# R131X.net
KiCad netlist of a schematic drawn in EAGLE
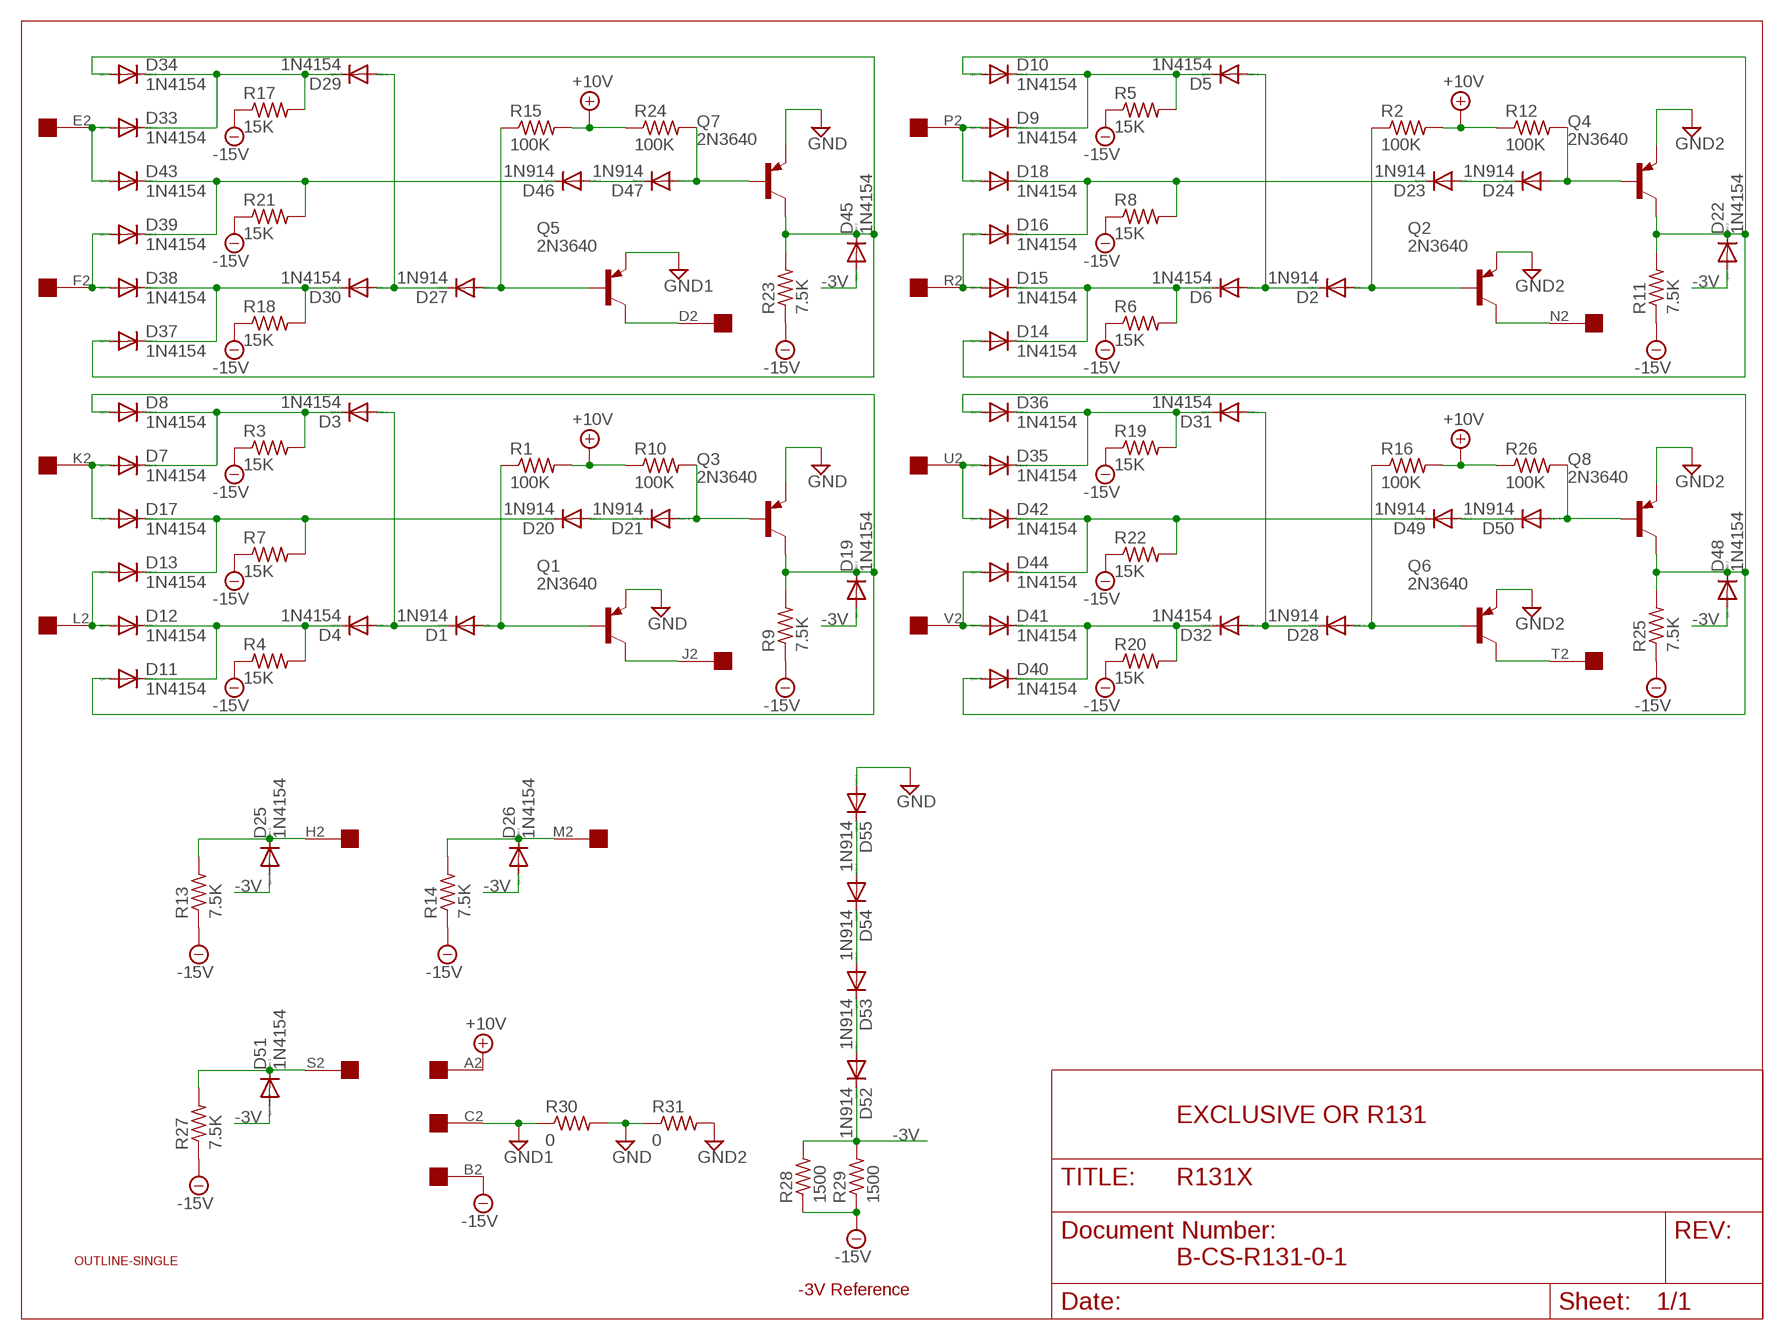
[diagram p0: schematic, sheet 1]

(export (version "E")
  (design (tool "Eeschema 10.0.6"))
  (components
    (comp (ref "D1")
      (value "1N914")
      (footprint "eagle-import:DO35-10")
      (libsource (lib "eagle-import") (part "1N4148DO35-10"))
    )
    (comp (ref "D2")
      (value "1N914")
      (footprint "eagle-import:DO35-10")
      (libsource (lib "eagle-import") (part "1N4148DO35-10"))
    )
    (comp (ref "D3")
      (value "1N4154")
      (footprint "eagle-import:DO35-10")
      (libsource (lib "eagle-import") (part "1N4148DO35-10"))
    )
    (comp (ref "D4")
      (value "1N4154")
      (footprint "eagle-import:DO35-10")
      (libsource (lib "eagle-import") (part "1N4148DO35-10"))
    )
    (comp (ref "D5")
      (value "1N4154")
      (footprint "eagle-import:DO35-10")
      (libsource (lib "eagle-import") (part "1N4148DO35-10"))
    )
    (comp (ref "D6")
      (value "1N4154")
      (footprint "eagle-import:DO35-10")
      (libsource (lib "eagle-import") (part "1N4148DO35-10"))
    )
    (comp (ref "D7")
      (value "1N4154")
      (footprint "eagle-import:DO35-10")
      (libsource (lib "eagle-import") (part "1N4148DO35-10"))
    )
    (comp (ref "D8")
      (value "1N4154")
      (footprint "eagle-import:DO35-10")
      (libsource (lib "eagle-import") (part "1N4148DO35-10"))
    )
    (comp (ref "D9")
      (value "1N4154")
      (footprint "eagle-import:DO35-10")
      (libsource (lib "eagle-import") (part "1N4148DO35-10"))
    )
    (comp (ref "D10")
      (value "1N4154")
      (footprint "eagle-import:DO35-10")
      (libsource (lib "eagle-import") (part "1N4148DO35-10"))
    )
    (comp (ref "D11")
      (value "1N4154")
      (footprint "eagle-import:DO35-10")
      (libsource (lib "eagle-import") (part "1N4148DO35-10"))
    )
    (comp (ref "D12")
      (value "1N4154")
      (footprint "eagle-import:DO35-10")
      (libsource (lib "eagle-import") (part "1N4148DO35-10"))
    )
    (comp (ref "D13")
      (value "1N4154")
      (footprint "eagle-import:DO35-10")
      (libsource (lib "eagle-import") (part "1N4148DO35-10"))
    )
    (comp (ref "D14")
      (value "1N4154")
      (footprint "eagle-import:DO35-10")
      (libsource (lib "eagle-import") (part "1N4148DO35-10"))
    )
    (comp (ref "D15")
      (value "1N4154")
      (footprint "eagle-import:DO35-10")
      (libsource (lib "eagle-import") (part "1N4148DO35-10"))
    )
    (comp (ref "D16")
      (value "1N4154")
      (footprint "eagle-import:DO35-10")
      (libsource (lib "eagle-import") (part "1N4148DO35-10"))
    )
    (comp (ref "D17")
      (value "1N4154")
      (footprint "eagle-import:DO35-10")
      (libsource (lib "eagle-import") (part "1N4148DO35-10"))
    )
    (comp (ref "D18")
      (value "1N4154")
      (footprint "eagle-import:DO35-10")
      (libsource (lib "eagle-import") (part "1N4148DO35-10"))
    )
    (comp (ref "D19")
      (value "1N4154")
      (footprint "eagle-import:DO35-10")
      (libsource (lib "eagle-import") (part "1N4148DO35-10"))
    )
    (comp (ref "D20")
      (value "1N914")
      (footprint "eagle-import:DO35-10")
      (libsource (lib "eagle-import") (part "1N4148DO35-10"))
    )
    (comp (ref "D21")
      (value "1N914")
      (footprint "eagle-import:DO35-10")
      (libsource (lib "eagle-import") (part "1N4148DO35-10"))
    )
    (comp (ref "D22")
      (value "1N4154")
      (footprint "eagle-import:DO35-10")
      (libsource (lib "eagle-import") (part "1N4148DO35-10"))
    )
    (comp (ref "D23")
      (value "1N914")
      (footprint "eagle-import:DO35-10")
      (libsource (lib "eagle-import") (part "1N4148DO35-10"))
    )
    (comp (ref "D24")
      (value "1N914")
      (footprint "eagle-import:DO35-10")
      (libsource (lib "eagle-import") (part "1N4148DO35-10"))
    )
    (comp (ref "D25")
      (value "1N4154")
      (footprint "eagle-import:DO35-10")
      (libsource (lib "eagle-import") (part "1N4148DO35-10"))
    )
    (comp (ref "D26")
      (value "1N4154")
      (footprint "eagle-import:DO35-10")
      (libsource (lib "eagle-import") (part "1N4148DO35-10"))
    )
    (comp (ref "D27")
      (value "1N914")
      (footprint "eagle-import:DO35-10")
      (libsource (lib "eagle-import") (part "1N4148DO35-10"))
    )
    (comp (ref "D28")
      (value "1N914")
      (footprint "eagle-import:DO35-10")
      (libsource (lib "eagle-import") (part "1N4148DO35-10"))
    )
    (comp (ref "D29")
      (value "1N4154")
      (footprint "eagle-import:DO35-10")
      (libsource (lib "eagle-import") (part "1N4148DO35-10"))
    )
    (comp (ref "D30")
      (value "1N4154")
      (footprint "eagle-import:DO35-10")
      (libsource (lib "eagle-import") (part "1N4148DO35-10"))
    )
    (comp (ref "D31")
      (value "1N4154")
      (footprint "eagle-import:DO35-10")
      (libsource (lib "eagle-import") (part "1N4148DO35-10"))
    )
    (comp (ref "D32")
      (value "1N4154")
      (footprint "eagle-import:DO35-10")
      (libsource (lib "eagle-import") (part "1N4148DO35-10"))
    )
    (comp (ref "D33")
      (value "1N4154")
      (footprint "eagle-import:DO35-10")
      (libsource (lib "eagle-import") (part "1N4148DO35-10"))
    )
    (comp (ref "D34")
      (value "1N4154")
      (footprint "eagle-import:DO35-10")
      (libsource (lib "eagle-import") (part "1N4148DO35-10"))
    )
    (comp (ref "D35")
      (value "1N4154")
      (footprint "eagle-import:DO35-10")
      (libsource (lib "eagle-import") (part "1N4148DO35-10"))
    )
    (comp (ref "D36")
      (value "1N4154")
      (footprint "eagle-import:DO35-10")
      (libsource (lib "eagle-import") (part "1N4148DO35-10"))
    )
    (comp (ref "D37")
      (value "1N4154")
      (footprint "eagle-import:DO35-10")
      (libsource (lib "eagle-import") (part "1N4148DO35-10"))
    )
    (comp (ref "D38")
      (value "1N4154")
      (footprint "eagle-import:DO35-10")
      (libsource (lib "eagle-import") (part "1N4148DO35-10"))
    )
    (comp (ref "D39")
      (value "1N4154")
      (footprint "eagle-import:DO35-10")
      (libsource (lib "eagle-import") (part "1N4148DO35-10"))
    )
    (comp (ref "D40")
      (value "1N4154")
      (footprint "eagle-import:DO35-10")
      (libsource (lib "eagle-import") (part "1N4148DO35-10"))
    )
    (comp (ref "D41")
      (value "1N4154")
      (footprint "eagle-import:DO35-10")
      (libsource (lib "eagle-import") (part "1N4148DO35-10"))
    )
    (comp (ref "D42")
      (value "1N4154")
      (footprint "eagle-import:DO35-10")
      (libsource (lib "eagle-import") (part "1N4148DO35-10"))
    )
    (comp (ref "D43")
      (value "1N4154")
      (footprint "eagle-import:DO35-10")
      (libsource (lib "eagle-import") (part "1N4148DO35-10"))
    )
    (comp (ref "D44")
      (value "1N4154")
      (footprint "eagle-import:DO35-10")
      (libsource (lib "eagle-import") (part "1N4148DO35-10"))
    )
    (comp (ref "D45")
      (value "1N4154")
      (footprint "eagle-import:DO35-10")
      (libsource (lib "eagle-import") (part "1N4148DO35-10"))
    )
    (comp (ref "D46")
      (value "1N914")
      (footprint "eagle-import:DO35-10")
      (libsource (lib "eagle-import") (part "1N4148DO35-10"))
    )
    (comp (ref "D47")
      (value "1N914")
      (footprint "eagle-import:DO35-10")
      (libsource (lib "eagle-import") (part "1N4148DO35-10"))
    )
    (comp (ref "D48")
      (value "1N4154")
      (footprint "eagle-import:DO35-10")
      (libsource (lib "eagle-import") (part "1N4148DO35-10"))
    )
    (comp (ref "D49")
      (value "1N914")
      (footprint "eagle-import:DO35-10")
      (libsource (lib "eagle-import") (part "1N4148DO35-10"))
    )
    (comp (ref "D50")
      (value "1N914")
      (footprint "eagle-import:DO35-10")
      (libsource (lib "eagle-import") (part "1N4148DO35-10"))
    )
    (comp (ref "D51")
      (value "1N4154")
      (footprint "eagle-import:DO35-10")
      (libsource (lib "eagle-import") (part "1N4148DO35-10"))
    )
    (comp (ref "D52")
      (value "1N914")
      (footprint "eagle-import:DO35-10")
      (libsource (lib "eagle-import") (part "1N4148DO35-10"))
    )
    (comp (ref "D53")
      (value "1N914")
      (footprint "eagle-import:DO35-10")
      (libsource (lib "eagle-import") (part "1N4148DO35-10"))
    )
    (comp (ref "D54")
      (value "1N914")
      (footprint "eagle-import:DO35-10")
      (libsource (lib "eagle-import") (part "1N4148DO35-10"))
    )
    (comp (ref "D55")
      (value "1N914")
      (footprint "eagle-import:DO35-10")
      (libsource (lib "eagle-import") (part "1N4148DO35-10"))
    )
    (comp (ref "Q1")
      (value "2N3640")
      (footprint "eagle-import:TO39")
      (libsource (lib "eagle-import") (part "2N3637"))
    )
    (comp (ref "Q2")
      (value "2N3640")
      (footprint "eagle-import:TO39")
      (libsource (lib "eagle-import") (part "2N3637"))
    )
    (comp (ref "Q3")
      (value "2N3640")
      (footprint "eagle-import:TO39")
      (libsource (lib "eagle-import") (part "2N3637"))
    )
    (comp (ref "Q4")
      (value "2N3640")
      (footprint "eagle-import:TO39")
      (libsource (lib "eagle-import") (part "2N3637"))
    )
    (comp (ref "Q5")
      (value "2N3640")
      (footprint "eagle-import:TO39")
      (libsource (lib "eagle-import") (part "2N3637"))
    )
    (comp (ref "Q6")
      (value "2N3640")
      (footprint "eagle-import:TO39")
      (libsource (lib "eagle-import") (part "2N3637"))
    )
    (comp (ref "Q7")
      (value "2N3640")
      (footprint "eagle-import:TO39")
      (libsource (lib "eagle-import") (part "2N3637"))
    )
    (comp (ref "Q8")
      (value "2N3640")
      (footprint "eagle-import:TO39")
      (libsource (lib "eagle-import") (part "2N3637"))
    )
    (comp (ref "R1")
      (value "100K")
      (footprint "eagle-import:0207_10")
      (libsource (lib "eagle-import") (part "R-US_0207/10"))
    )
    (comp (ref "R2")
      (value "100K")
      (footprint "eagle-import:0207_10")
      (libsource (lib "eagle-import") (part "R-US_0207/10"))
    )
    (comp (ref "R3")
      (value "15K")
      (footprint "eagle-import:0207_10")
      (libsource (lib "eagle-import") (part "R-US_0207/10"))
    )
    (comp (ref "R4")
      (value "15K")
      (footprint "eagle-import:0207_10")
      (libsource (lib "eagle-import") (part "R-US_0207/10"))
    )
    (comp (ref "R5")
      (value "15K")
      (footprint "eagle-import:0207_10")
      (libsource (lib "eagle-import") (part "R-US_0207/10"))
    )
    (comp (ref "R6")
      (value "15K")
      (footprint "eagle-import:0207_10")
      (libsource (lib "eagle-import") (part "R-US_0207/10"))
    )
    (comp (ref "R7")
      (value "15K")
      (footprint "eagle-import:0207_10")
      (libsource (lib "eagle-import") (part "R-US_0207/10"))
    )
    (comp (ref "R8")
      (value "15K")
      (footprint "eagle-import:0207_10")
      (libsource (lib "eagle-import") (part "R-US_0207/10"))
    )
    (comp (ref "R9")
      (value "7.5K")
      (footprint "eagle-import:0207_10")
      (libsource (lib "eagle-import") (part "R-US_0207/10"))
    )
    (comp (ref "R10")
      (value "100K")
      (footprint "eagle-import:0207_10")
      (libsource (lib "eagle-import") (part "R-US_0207/10"))
    )
    (comp (ref "R11")
      (value "7.5K")
      (footprint "eagle-import:0207_10")
      (libsource (lib "eagle-import") (part "R-US_0207/10"))
    )
    (comp (ref "R12")
      (value "100K")
      (footprint "eagle-import:0207_10")
      (libsource (lib "eagle-import") (part "R-US_0207/10"))
    )
    (comp (ref "R13")
      (value "7.5K")
      (footprint "eagle-import:0207_10")
      (libsource (lib "eagle-import") (part "R-US_0207/10"))
    )
    (comp (ref "R14")
      (value "7.5K")
      (footprint "eagle-import:0207_10")
      (libsource (lib "eagle-import") (part "R-US_0207/10"))
    )
    (comp (ref "R15")
      (value "100K")
      (footprint "eagle-import:0207_10")
      (libsource (lib "eagle-import") (part "R-US_0207/10"))
    )
    (comp (ref "R16")
      (value "100K")
      (footprint "eagle-import:0207_10")
      (libsource (lib "eagle-import") (part "R-US_0207/10"))
    )
    (comp (ref "R17")
      (value "15K")
      (footprint "eagle-import:0207_10")
      (libsource (lib "eagle-import") (part "R-US_0207/10"))
    )
    (comp (ref "R18")
      (value "15K")
      (footprint "eagle-import:0207_10")
      (libsource (lib "eagle-import") (part "R-US_0207/10"))
    )
    (comp (ref "R19")
      (value "15K")
      (footprint "eagle-import:0207_10")
      (libsource (lib "eagle-import") (part "R-US_0207/10"))
    )
    (comp (ref "R20")
      (value "15K")
      (footprint "eagle-import:0207_10")
      (libsource (lib "eagle-import") (part "R-US_0207/10"))
    )
    (comp (ref "R21")
      (value "15K")
      (footprint "eagle-import:0207_10")
      (libsource (lib "eagle-import") (part "R-US_0207/10"))
    )
    (comp (ref "R22")
      (value "15K")
      (footprint "eagle-import:0207_10")
      (libsource (lib "eagle-import") (part "R-US_0207/10"))
    )
    (comp (ref "R23")
      (value "7.5K")
      (footprint "eagle-import:0207_10")
      (libsource (lib "eagle-import") (part "R-US_0207/10"))
    )
    (comp (ref "R24")
      (value "100K")
      (footprint "eagle-import:0207_10")
      (libsource (lib "eagle-import") (part "R-US_0207/10"))
    )
    (comp (ref "R25")
      (value "7.5K")
      (footprint "eagle-import:0207_10")
      (libsource (lib "eagle-import") (part "R-US_0207/10"))
    )
    (comp (ref "R26")
      (value "100K")
      (footprint "eagle-import:0207_10")
      (libsource (lib "eagle-import") (part "R-US_0207/10"))
    )
    (comp (ref "R27")
      (value "7.5K")
      (footprint "eagle-import:0207_10")
      (libsource (lib "eagle-import") (part "R-US_0207/10"))
    )
    (comp (ref "R28")
      (value "1500")
      (footprint "eagle-import:0207_10")
      (libsource (lib "eagle-import") (part "R-US_0207/10"))
    )
    (comp (ref "R29")
      (value "1500")
      (footprint "eagle-import:0207_10")
      (libsource (lib "eagle-import") (part "R-US_0207/10"))
    )
    (comp (ref "R30")
      (value "0")
      (footprint "eagle-import:0207_10")
      (libsource (lib "eagle-import") (part "R-US_0207/10"))
    )
    (comp (ref "R31")
      (value "0")
      (footprint "eagle-import:0207_10")
      (libsource (lib "eagle-import") (part "R-US_0207/10"))
    )
    (comp (ref "U$1")
      (value "OUTLINE-SINGLE")
      (footprint "eagle-import:SINGLE")
      (libsource (lib "eagle-import") (part "OUTLINE-SINGLE"))
    )
    (comp (ref "U$2")
      (value "EDGE-1")
      (footprint "eagle-import:EDGE-CON1")
      (libsource (lib "eagle-import") (part "EDGE-1"))
    )
  )
  (nets
    (net (code "1") (name "+10V") (class "Default")
      (node (ref "R1") (pin "2") (pinfunction "2_2") (pintype "passive"))
      (node (ref "R10") (pin "1") (pinfunction "1_1") (pintype "passive"))
      (node (ref "R12") (pin "1") (pinfunction "1_1") (pintype "passive"))
      (node (ref "R15") (pin "2") (pinfunction "2_2") (pintype "passive"))
      (node (ref "R16") (pin "2") (pinfunction "2_2") (pintype "passive"))
      (node (ref "R2") (pin "2") (pinfunction "2_2") (pintype "passive"))
      (node (ref "R24") (pin "1") (pinfunction "1_1") (pintype "passive"))
      (node (ref "R26") (pin "1") (pinfunction "1_1") (pintype "passive"))
      (node (ref "U$2") (pin "A2") (pinfunction "1_A2") (pintype "bidirectional"))
    )
    (net (code "2") (name "-15V") (class "Default")
      (node (ref "R11") (pin "1") (pinfunction "1_1") (pintype "passive"))
      (node (ref "R13") (pin "1") (pinfunction "1_1") (pintype "passive"))
      (node (ref "R14") (pin "1") (pinfunction "1_1") (pintype "passive"))
      (node (ref "R17") (pin "1") (pinfunction "1_1") (pintype "passive"))
      (node (ref "R18") (pin "1") (pinfunction "1_1") (pintype "passive"))
      (node (ref "R19") (pin "1") (pinfunction "1_1") (pintype "passive"))
      (node (ref "R20") (pin "1") (pinfunction "1_1") (pintype "passive"))
      (node (ref "R21") (pin "1") (pinfunction "1_1") (pintype "passive"))
      (node (ref "R22") (pin "1") (pinfunction "1_1") (pintype "passive"))
      (node (ref "R23") (pin "1") (pinfunction "1_1") (pintype "passive"))
      (node (ref "R25") (pin "1") (pinfunction "1_1") (pintype "passive"))
      (node (ref "R27") (pin "1") (pinfunction "1_1") (pintype "passive"))
      (node (ref "R28") (pin "1") (pinfunction "1_1") (pintype "passive"))
      (node (ref "R29") (pin "1") (pinfunction "1_1") (pintype "passive"))
      (node (ref "R3") (pin "1") (pinfunction "1_1") (pintype "passive"))
      (node (ref "R4") (pin "1") (pinfunction "1_1") (pintype "passive"))
      (node (ref "R5") (pin "1") (pinfunction "1_1") (pintype "passive"))
      (node (ref "R6") (pin "1") (pinfunction "1_1") (pintype "passive"))
      (node (ref "R7") (pin "1") (pinfunction "1_1") (pintype "passive"))
      (node (ref "R8") (pin "1") (pinfunction "1_1") (pintype "passive"))
      (node (ref "R9") (pin "1") (pinfunction "1_1") (pintype "passive"))
      (node (ref "U$2") (pin "B2") (pinfunction "1_B2") (pintype "bidirectional"))
    )
    (net (code "3") (name "/-3V") (class "Default")
      (node (ref "D19") (pin "A") (pinfunction "A_A") (pintype "passive"))
      (node (ref "D22") (pin "A") (pinfunction "A_A") (pintype "passive"))
      (node (ref "D25") (pin "A") (pinfunction "A_A") (pintype "passive"))
      (node (ref "D26") (pin "A") (pinfunction "A_A") (pintype "passive"))
      (node (ref "D45") (pin "A") (pinfunction "A_A") (pintype "passive"))
      (node (ref "D48") (pin "A") (pinfunction "A_A") (pintype "passive"))
      (node (ref "D51") (pin "A") (pinfunction "A_A") (pintype "passive"))
      (node (ref "D52") (pin "C") (pinfunction "C_C") (pintype "passive"))
      (node (ref "R28") (pin "2") (pinfunction "2_2") (pintype "passive"))
      (node (ref "R29") (pin "2") (pinfunction "2_2") (pintype "passive"))
    )
    (net (code "4") (name "GND") (class "Default")
      (node (ref "D55") (pin "A") (pinfunction "A_A") (pintype "passive"))
      (node (ref "Q1") (pin "1") (pinfunction "E_1") (pintype "passive"))
      (node (ref "Q3") (pin "1") (pinfunction "E_1") (pintype "passive"))
      (node (ref "Q7") (pin "1") (pinfunction "E_1") (pintype "passive"))
      (node (ref "R30") (pin "2") (pinfunction "2_2") (pintype "passive"))
      (node (ref "R31") (pin "1") (pinfunction "1_1") (pintype "passive"))
    )
    (net (code "5") (name "GND1") (class "Default")
      (node (ref "Q5") (pin "1") (pinfunction "E_1") (pintype "passive"))
      (node (ref "R30") (pin "1") (pinfunction "1_1") (pintype "passive"))
      (node (ref "U$2") (pin "C2") (pinfunction "1_C2") (pintype "bidirectional"))
    )
    (net (code "6") (name "GND2") (class "Default")
      (node (ref "Q2") (pin "1") (pinfunction "E_1") (pintype "passive"))
      (node (ref "Q4") (pin "1") (pinfunction "E_1") (pintype "passive"))
      (node (ref "Q6") (pin "1") (pinfunction "E_1") (pintype "passive"))
      (node (ref "Q8") (pin "1") (pinfunction "E_1") (pintype "passive"))
      (node (ref "R31") (pin "2") (pinfunction "2_2") (pintype "passive"))
    )
    (net (code "7") (name "Net-(D1-PadC)") (class "Default")
      (node (ref "D1") (pin "C") (pinfunction "C_C") (pintype "passive"))
      (node (ref "D3") (pin "A") (pinfunction "A_A") (pintype "passive"))
      (node (ref "D4") (pin "A") (pinfunction "A_A") (pintype "passive"))
    )
    (net (code "8") (name "Net-(D2-PadC)") (class "Default")
      (node (ref "D2") (pin "C") (pinfunction "C_C") (pintype "passive"))
      (node (ref "D5") (pin "A") (pinfunction "A_A") (pintype "passive"))
      (node (ref "D6") (pin "A") (pinfunction "A_A") (pintype "passive"))
    )
    (net (code "9") (name "Net-(D3-PadC)") (class "Default")
      (node (ref "D3") (pin "C") (pinfunction "C_C") (pintype "passive"))
      (node (ref "D7") (pin "C") (pinfunction "C_C") (pintype "passive"))
      (node (ref "D8") (pin "C") (pinfunction "C_C") (pintype "passive"))
      (node (ref "R3") (pin "2") (pinfunction "2_2") (pintype "passive"))
    )
    (net (code "10") (name "Net-(D10-PadC)") (class "Default")
      (node (ref "D10") (pin "C") (pinfunction "C_C") (pintype "passive"))
      (node (ref "D5") (pin "C") (pinfunction "C_C") (pintype "passive"))
      (node (ref "D9") (pin "C") (pinfunction "C_C") (pintype "passive"))
      (node (ref "R5") (pin "2") (pinfunction "2_2") (pintype "passive"))
    )
    (net (code "11") (name "Net-(D11-PadC)") (class "Default")
      (node (ref "D11") (pin "C") (pinfunction "C_C") (pintype "passive"))
      (node (ref "D12") (pin "C") (pinfunction "C_C") (pintype "passive"))
      (node (ref "D4") (pin "C") (pinfunction "C_C") (pintype "passive"))
      (node (ref "R4") (pin "2") (pinfunction "2_2") (pintype "passive"))
    )
    (net (code "12") (name "Net-(D13-PadC)") (class "Default")
      (node (ref "D13") (pin "C") (pinfunction "C_C") (pintype "passive"))
      (node (ref "D17") (pin "C") (pinfunction "C_C") (pintype "passive"))
      (node (ref "D20") (pin "C") (pinfunction "C_C") (pintype "passive"))
      (node (ref "R7") (pin "2") (pinfunction "2_2") (pintype "passive"))
    )
    (net (code "13") (name "Net-(D14-PadC)") (class "Default")
      (node (ref "D14") (pin "C") (pinfunction "C_C") (pintype "passive"))
      (node (ref "D15") (pin "C") (pinfunction "C_C") (pintype "passive"))
      (node (ref "D6") (pin "C") (pinfunction "C_C") (pintype "passive"))
      (node (ref "R6") (pin "2") (pinfunction "2_2") (pintype "passive"))
    )
    (net (code "14") (name "Net-(D16-PadC)") (class "Default")
      (node (ref "D16") (pin "C") (pinfunction "C_C") (pintype "passive"))
      (node (ref "D18") (pin "C") (pinfunction "C_C") (pintype "passive"))
      (node (ref "D23") (pin "C") (pinfunction "C_C") (pintype "passive"))
      (node (ref "R8") (pin "2") (pinfunction "2_2") (pintype "passive"))
    )
    (net (code "15") (name "Net-(D20-PadA)") (class "Default")
      (node (ref "D20") (pin "A") (pinfunction "A_A") (pintype "passive"))
      (node (ref "D21") (pin "C") (pinfunction "C_C") (pintype "passive"))
    )
    (net (code "16") (name "Net-(D23-PadA)") (class "Default")
      (node (ref "D23") (pin "A") (pinfunction "A_A") (pintype "passive"))
      (node (ref "D24") (pin "C") (pinfunction "C_C") (pintype "passive"))
    )
    (net (code "17") (name "Net-(D27-PadC)") (class "Default")
      (node (ref "D27") (pin "C") (pinfunction "C_C") (pintype "passive"))
      (node (ref "D29") (pin "A") (pinfunction "A_A") (pintype "passive"))
      (node (ref "D30") (pin "A") (pinfunction "A_A") (pintype "passive"))
    )
    (net (code "18") (name "Net-(D28-PadC)") (class "Default")
      (node (ref "D28") (pin "C") (pinfunction "C_C") (pintype "passive"))
      (node (ref "D31") (pin "A") (pinfunction "A_A") (pintype "passive"))
      (node (ref "D32") (pin "A") (pinfunction "A_A") (pintype "passive"))
    )
    (net (code "19") (name "Net-(D29-PadC)") (class "Default")
      (node (ref "D29") (pin "C") (pinfunction "C_C") (pintype "passive"))
      (node (ref "D33") (pin "C") (pinfunction "C_C") (pintype "passive"))
      (node (ref "D34") (pin "C") (pinfunction "C_C") (pintype "passive"))
      (node (ref "R17") (pin "2") (pinfunction "2_2") (pintype "passive"))
    )
    (net (code "20") (name "Net-(D30-PadC)") (class "Default")
      (node (ref "D30") (pin "C") (pinfunction "C_C") (pintype "passive"))
      (node (ref "D37") (pin "C") (pinfunction "C_C") (pintype "passive"))
      (node (ref "D38") (pin "C") (pinfunction "C_C") (pintype "passive"))
      (node (ref "R18") (pin "2") (pinfunction "2_2") (pintype "passive"))
    )
    (net (code "21") (name "Net-(D31-PadC)") (class "Default")
      (node (ref "D31") (pin "C") (pinfunction "C_C") (pintype "passive"))
      (node (ref "D35") (pin "C") (pinfunction "C_C") (pintype "passive"))
      (node (ref "D36") (pin "C") (pinfunction "C_C") (pintype "passive"))
      (node (ref "R19") (pin "2") (pinfunction "2_2") (pintype "passive"))
    )
    (net (code "22") (name "Net-(D32-PadC)") (class "Default")
      (node (ref "D32") (pin "C") (pinfunction "C_C") (pintype "passive"))
      (node (ref "D40") (pin "C") (pinfunction "C_C") (pintype "passive"))
      (node (ref "D41") (pin "C") (pinfunction "C_C") (pintype "passive"))
      (node (ref "R20") (pin "2") (pinfunction "2_2") (pintype "passive"))
    )
    (net (code "23") (name "Net-(D39-PadC)") (class "Default")
      (node (ref "D39") (pin "C") (pinfunction "C_C") (pintype "passive"))
      (node (ref "D43") (pin "C") (pinfunction "C_C") (pintype "passive"))
      (node (ref "D46") (pin "C") (pinfunction "C_C") (pintype "passive"))
      (node (ref "R21") (pin "2") (pinfunction "2_2") (pintype "passive"))
    )
    (net (code "24") (name "Net-(D42-PadC)") (class "Default")
      (node (ref "D42") (pin "C") (pinfunction "C_C") (pintype "passive"))
      (node (ref "D44") (pin "C") (pinfunction "C_C") (pintype "passive"))
      (node (ref "D49") (pin "C") (pinfunction "C_C") (pintype "passive"))
      (node (ref "R22") (pin "2") (pinfunction "2_2") (pintype "passive"))
    )
    (net (code "25") (name "Net-(D46-PadA)") (class "Default")
      (node (ref "D46") (pin "A") (pinfunction "A_A") (pintype "passive"))
      (node (ref "D47") (pin "C") (pinfunction "C_C") (pintype "passive"))
    )
    (net (code "26") (name "Net-(D49-PadA)") (class "Default")
      (node (ref "D49") (pin "A") (pinfunction "A_A") (pintype "passive"))
      (node (ref "D50") (pin "C") (pinfunction "C_C") (pintype "passive"))
    )
    (net (code "27") (name "Net-(D52-PadA)") (class "Default")
      (node (ref "D52") (pin "A") (pinfunction "A_A") (pintype "passive"))
      (node (ref "D53") (pin "C") (pinfunction "C_C") (pintype "passive"))
    )
    (net (code "28") (name "Net-(D53-PadA)") (class "Default")
      (node (ref "D53") (pin "A") (pinfunction "A_A") (pintype "passive"))
      (node (ref "D54") (pin "C") (pinfunction "C_C") (pintype "passive"))
    )
    (net (code "29") (name "Net-(D54-PadA)") (class "Default")
      (node (ref "D54") (pin "A") (pinfunction "A_A") (pintype "passive"))
      (node (ref "D55") (pin "C") (pinfunction "C_C") (pintype "passive"))
    )
    (net (code "30") (name "Net-(Q1-B)") (class "Default")
      (node (ref "D1") (pin "A") (pinfunction "A_A") (pintype "passive"))
      (node (ref "Q1") (pin "2") (pinfunction "B_2") (pintype "passive"))
      (node (ref "R1") (pin "1") (pinfunction "1_1") (pintype "passive"))
    )
    (net (code "31") (name "Net-(Q1-C)") (class "Default")
      (node (ref "Q1") (pin "3") (pinfunction "C_3") (pintype "passive"))
      (node (ref "U$2") (pin "J2") (pinfunction "1_J2") (pintype "bidirectional"))
    )
    (net (code "32") (name "Net-(Q2-B)") (class "Default")
      (node (ref "D2") (pin "A") (pinfunction "A_A") (pintype "passive"))
      (node (ref "Q2") (pin "2") (pinfunction "B_2") (pintype "passive"))
      (node (ref "R2") (pin "1") (pinfunction "1_1") (pintype "passive"))
    )
    (net (code "33") (name "Net-(Q2-C)") (class "Default")
      (node (ref "Q2") (pin "3") (pinfunction "C_3") (pintype "passive"))
      (node (ref "U$2") (pin "N2") (pinfunction "1_N2") (pintype "bidirectional"))
    )
    (net (code "34") (name "Net-(Q3-B)") (class "Default")
      (node (ref "D21") (pin "A") (pinfunction "A_A") (pintype "passive"))
      (node (ref "Q3") (pin "2") (pinfunction "B_2") (pintype "passive"))
      (node (ref "R10") (pin "2") (pinfunction "2_2") (pintype "passive"))
    )
    (net (code "35") (name "Net-(Q3-C)") (class "Default")
      (node (ref "D11") (pin "A") (pinfunction "A_A") (pintype "passive"))
      (node (ref "D19") (pin "C") (pinfunction "C_C") (pintype "passive"))
      (node (ref "D8") (pin "A") (pinfunction "A_A") (pintype "passive"))
      (node (ref "Q3") (pin "3") (pinfunction "C_3") (pintype "passive"))
      (node (ref "R9") (pin "2") (pinfunction "2_2") (pintype "passive"))
    )
    (net (code "36") (name "Net-(Q4-B)") (class "Default")
      (node (ref "D24") (pin "A") (pinfunction "A_A") (pintype "passive"))
      (node (ref "Q4") (pin "2") (pinfunction "B_2") (pintype "passive"))
      (node (ref "R12") (pin "2") (pinfunction "2_2") (pintype "passive"))
    )
    (net (code "37") (name "Net-(Q4-C)") (class "Default")
      (node (ref "D10") (pin "A") (pinfunction "A_A") (pintype "passive"))
      (node (ref "D14") (pin "A") (pinfunction "A_A") (pintype "passive"))
      (node (ref "D22") (pin "C") (pinfunction "C_C") (pintype "passive"))
      (node (ref "Q4") (pin "3") (pinfunction "C_3") (pintype "passive"))
      (node (ref "R11") (pin "2") (pinfunction "2_2") (pintype "passive"))
    )
    (net (code "38") (name "Net-(Q5-B)") (class "Default")
      (node (ref "D27") (pin "A") (pinfunction "A_A") (pintype "passive"))
      (node (ref "Q5") (pin "2") (pinfunction "B_2") (pintype "passive"))
      (node (ref "R15") (pin "1") (pinfunction "1_1") (pintype "passive"))
    )
    (net (code "39") (name "Net-(Q5-C)") (class "Default")
      (node (ref "Q5") (pin "3") (pinfunction "C_3") (pintype "passive"))
      (node (ref "U$2") (pin "D2") (pinfunction "1_D2") (pintype "bidirectional"))
    )
    (net (code "40") (name "Net-(Q6-B)") (class "Default")
      (node (ref "D28") (pin "A") (pinfunction "A_A") (pintype "passive"))
      (node (ref "Q6") (pin "2") (pinfunction "B_2") (pintype "passive"))
      (node (ref "R16") (pin "1") (pinfunction "1_1") (pintype "passive"))
    )
    (net (code "41") (name "Net-(Q6-C)") (class "Default")
      (node (ref "Q6") (pin "3") (pinfunction "C_3") (pintype "passive"))
      (node (ref "U$2") (pin "T2") (pinfunction "1_T2") (pintype "bidirectional"))
    )
    (net (code "42") (name "Net-(Q7-B)") (class "Default")
      (node (ref "D47") (pin "A") (pinfunction "A_A") (pintype "passive"))
      (node (ref "Q7") (pin "2") (pinfunction "B_2") (pintype "passive"))
      (node (ref "R24") (pin "2") (pinfunction "2_2") (pintype "passive"))
    )
    (net (code "43") (name "Net-(Q7-C)") (class "Default")
      (node (ref "D34") (pin "A") (pinfunction "A_A") (pintype "passive"))
      (node (ref "D37") (pin "A") (pinfunction "A_A") (pintype "passive"))
      (node (ref "D45") (pin "C") (pinfunction "C_C") (pintype "passive"))
      (node (ref "Q7") (pin "3") (pinfunction "C_3") (pintype "passive"))
      (node (ref "R23") (pin "2") (pinfunction "2_2") (pintype "passive"))
    )
    (net (code "44") (name "Net-(Q8-B)") (class "Default")
      (node (ref "D50") (pin "A") (pinfunction "A_A") (pintype "passive"))
      (node (ref "Q8") (pin "2") (pinfunction "B_2") (pintype "passive"))
      (node (ref "R26") (pin "2") (pinfunction "2_2") (pintype "passive"))
    )
    (net (code "45") (name "Net-(Q8-C)") (class "Default")
      (node (ref "D36") (pin "A") (pinfunction "A_A") (pintype "passive"))
      (node (ref "D40") (pin "A") (pinfunction "A_A") (pintype "passive"))
      (node (ref "D48") (pin "C") (pinfunction "C_C") (pintype "passive"))
      (node (ref "Q8") (pin "3") (pinfunction "C_3") (pintype "passive"))
      (node (ref "R25") (pin "2") (pinfunction "2_2") (pintype "passive"))
    )
    (net (code "46") (name "Net-(U$2E-1)") (class "Default")
      (node (ref "D33") (pin "A") (pinfunction "A_A") (pintype "passive"))
      (node (ref "D43") (pin "A") (pinfunction "A_A") (pintype "passive"))
      (node (ref "U$2") (pin "E2") (pinfunction "1_E2") (pintype "bidirectional"))
    )
    (net (code "47") (name "Net-(U$2F-1)") (class "Default")
      (node (ref "D38") (pin "A") (pinfunction "A_A") (pintype "passive"))
      (node (ref "D39") (pin "A") (pinfunction "A_A") (pintype "passive"))
      (node (ref "U$2") (pin "F2") (pinfunction "1_F2") (pintype "bidirectional"))
    )
    (net (code "48") (name "Net-(U$2G-1)") (class "Default")
      (node (ref "D25") (pin "C") (pinfunction "C_C") (pintype "passive"))
      (node (ref "R13") (pin "2") (pinfunction "2_2") (pintype "passive"))
      (node (ref "U$2") (pin "H2") (pinfunction "1_H2") (pintype "bidirectional"))
    )
    (net (code "49") (name "Net-(U$2I-1)") (class "Default")
      (node (ref "D17") (pin "A") (pinfunction "A_A") (pintype "passive"))
      (node (ref "D7") (pin "A") (pinfunction "A_A") (pintype "passive"))
      (node (ref "U$2") (pin "K2") (pinfunction "1_K2") (pintype "bidirectional"))
    )
    (net (code "50") (name "Net-(U$2J-1)") (class "Default")
      (node (ref "D12") (pin "A") (pinfunction "A_A") (pintype "passive"))
      (node (ref "D13") (pin "A") (pinfunction "A_A") (pintype "passive"))
      (node (ref "U$2") (pin "L2") (pinfunction "1_L2") (pintype "bidirectional"))
    )
    (net (code "51") (name "Net-(U$2K-1)") (class "Default")
      (node (ref "D26") (pin "C") (pinfunction "C_C") (pintype "passive"))
      (node (ref "R14") (pin "2") (pinfunction "2_2") (pintype "passive"))
      (node (ref "U$2") (pin "M2") (pinfunction "1_M2") (pintype "bidirectional"))
    )
    (net (code "52") (name "Net-(U$2M-1)") (class "Default")
      (node (ref "D18") (pin "A") (pinfunction "A_A") (pintype "passive"))
      (node (ref "D9") (pin "A") (pinfunction "A_A") (pintype "passive"))
      (node (ref "U$2") (pin "P2") (pinfunction "1_P2") (pintype "bidirectional"))
    )
    (net (code "53") (name "Net-(U$2N-1)") (class "Default")
      (node (ref "D15") (pin "A") (pinfunction "A_A") (pintype "passive"))
      (node (ref "D16") (pin "A") (pinfunction "A_A") (pintype "passive"))
      (node (ref "U$2") (pin "R2") (pinfunction "1_R2") (pintype "bidirectional"))
    )
    (net (code "54") (name "Net-(U$2O-1)") (class "Default")
      (node (ref "D51") (pin "C") (pinfunction "C_C") (pintype "passive"))
      (node (ref "R27") (pin "2") (pinfunction "2_2") (pintype "passive"))
      (node (ref "U$2") (pin "S2") (pinfunction "1_S2") (pintype "bidirectional"))
    )
    (net (code "55") (name "Net-(U$2Q-1)") (class "Default")
      (node (ref "D35") (pin "A") (pinfunction "A_A") (pintype "passive"))
      (node (ref "D42") (pin "A") (pinfunction "A_A") (pintype "passive"))
      (node (ref "U$2") (pin "U2") (pinfunction "1_U2") (pintype "bidirectional"))
    )
    (net (code "56") (name "Net-(U$2R-1)") (class "Default")
      (node (ref "D41") (pin "A") (pinfunction "A_A") (pintype "passive"))
      (node (ref "D44") (pin "A") (pinfunction "A_A") (pintype "passive"))
      (node (ref "U$2") (pin "V2") (pinfunction "1_V2") (pintype "bidirectional"))
    )
  )
)
